# CubSat3.net
KiCad netlist of a schematic drawn in Altium Designer
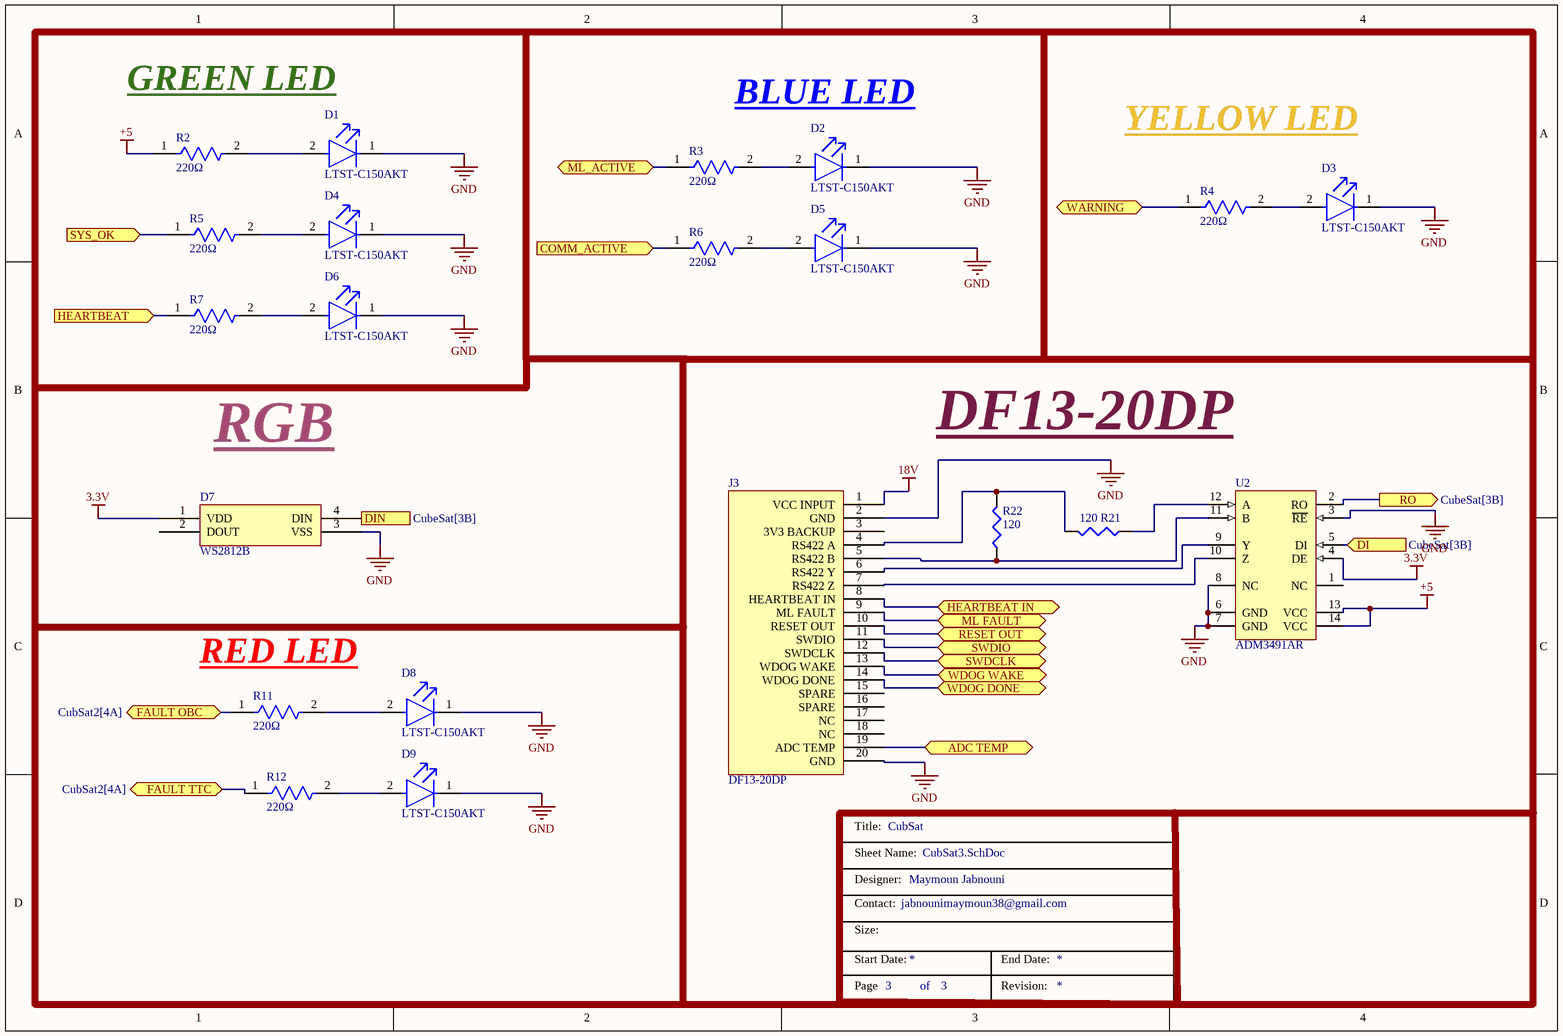
[diagram p0: CubSat3.SchDoc]

(export (version "E")
  (design (tool "Eeschema 10.0.6"))
  (components
    (comp (ref "D1")
      (value "LTST-C150AKT")
      (footprint "FP-LTST-C150AKT-MFG")
      (description "LED AMBER CLEAR SMD")
      (fields
        (field (name "MANUFACTURER") "Lite-On")
        (field (name "OCTOPART") "https://octopart.com/ltst-c150akt-lite-on-549804")
      )
      (libsource (lib "Altium Content Vault") (part "8706943c75ba83719d021d2fdc84c58"))
    )
    (comp (ref "D2")
      (value "LTST-C150AKT")
      (footprint "FP-LTST-C150AKT-MFG")
      (description "LED AMBER CLEAR SMD")
      (fields
        (field (name "MANUFACTURER") "Lite-On")
        (field (name "OCTOPART") "https://octopart.com/ltst-c150akt-lite-on-549804")
      )
      (libsource (lib "Altium Content Vault") (part "8706943c75ba83719d021d2fdc84c58"))
    )
    (comp (ref "D3")
      (value "LTST-C150AKT")
      (footprint "FP-LTST-C150AKT-MFG")
      (description "LED AMBER CLEAR SMD")
      (fields
        (field (name "MANUFACTURER") "Lite-On")
        (field (name "OCTOPART") "https://octopart.com/ltst-c150akt-lite-on-549804")
      )
      (libsource (lib "Altium Content Vault") (part "8706943c75ba83719d021d2fdc84c58"))
    )
    (comp (ref "D4")
      (value "LTST-C150AKT")
      (footprint "FP-LTST-C150AKT-MFG")
      (description "LED AMBER CLEAR SMD")
      (fields
        (field (name "MANUFACTURER") "Lite-On")
        (field (name "OCTOPART") "https://octopart.com/ltst-c150akt-lite-on-549804")
      )
      (libsource (lib "Altium Content Vault") (part "8706943c75ba83719d021d2fdc84c58"))
    )
    (comp (ref "D5")
      (value "LTST-C150AKT")
      (footprint "FP-LTST-C150AKT-MFG")
      (description "LED AMBER CLEAR SMD")
      (fields
        (field (name "MANUFACTURER") "Lite-On")
        (field (name "OCTOPART") "https://octopart.com/ltst-c150akt-lite-on-549804")
      )
      (libsource (lib "Altium Content Vault") (part "8706943c75ba83719d021d2fdc84c58"))
    )
    (comp (ref "D6")
      (value "LTST-C150AKT")
      (footprint "FP-LTST-C150AKT-MFG")
      (description "LED AMBER CLEAR SMD")
      (fields
        (field (name "MANUFACTURER") "Lite-On")
        (field (name "OCTOPART") "https://octopart.com/ltst-c150akt-lite-on-549804")
      )
      (libsource (lib "Altium Content Vault") (part "8706943c75ba83719d021d2fdc84c58"))
    )
    (comp (ref "D7") (value "WS2812B") (footprint "WS2812B") (libsource (lib "CubSat") (part "RGB_LED")))
    (comp (ref "D8")
      (value "LTST-C150AKT")
      (footprint "FP-LTST-C150AKT-MFG")
      (description "LED AMBER CLEAR SMD")
      (fields
        (field (name "MANUFACTURER") "Lite-On")
        (field (name "OCTOPART") "https://octopart.com/ltst-c150akt-lite-on-549804")
      )
      (libsource (lib "Altium Content Vault") (part "8706943c75ba83719d021d2fdc84c58"))
    )
    (comp (ref "D9")
      (value "LTST-C150AKT")
      (footprint "FP-LTST-C150AKT-MFG")
      (description "LED AMBER CLEAR SMD")
      (fields
        (field (name "MANUFACTURER") "Lite-On")
        (field (name "OCTOPART") "https://octopart.com/ltst-c150akt-lite-on-549804")
      )
      (libsource (lib "Altium Content Vault") (part "8706943c75ba83719d021d2fdc84c58"))
    )
    (comp (ref "J3")
      (value "DF13-20DP")
      (footprint "DF13-20DP")
      (libsource (lib "CubSat") (part "DF13-20DP"))
    )
    (comp (ref "R2")
      (value "220Ω")
      (footprint "FP-RMCF0603-MFG")
      (description "220Ω ±5% 0.1W 0603 Thick Film Chip Resistor AEC-Q200 compliant")
      (fields (field (name "TOLERANCE") "5%"))
      (libsource (lib "Altium Content Vault") (part "1029c3af85768c4190bb7ad29bc67b5"))
    )
    (comp (ref "R3")
      (value "220Ω")
      (footprint "FP-RMCF0603-MFG")
      (description "220Ω ±5% 0.1W 0603 Thick Film Chip Resistor AEC-Q200 compliant")
      (fields (field (name "TOLERANCE") "5%"))
      (libsource (lib "Altium Content Vault") (part "1029c3af85768c4190bb7ad29bc67b5"))
    )
    (comp (ref "R4")
      (value "220Ω")
      (footprint "FP-RMCF0603-MFG")
      (description "220Ω ±5% 0.1W 0603 Thick Film Chip Resistor AEC-Q200 compliant")
      (fields (field (name "TOLERANCE") "5%"))
      (libsource (lib "Altium Content Vault") (part "1029c3af85768c4190bb7ad29bc67b5"))
    )
    (comp (ref "R5")
      (value "220Ω")
      (footprint "FP-RMCF0603-MFG")
      (description "220Ω ±5% 0.1W 0603 Thick Film Chip Resistor AEC-Q200 compliant")
      (fields (field (name "TOLERANCE") "5%"))
      (libsource (lib "Altium Content Vault") (part "1029c3af85768c4190bb7ad29bc67b5"))
    )
    (comp (ref "R6")
      (value "220Ω")
      (footprint "FP-RMCF0603-MFG")
      (description "220Ω ±5% 0.1W 0603 Thick Film Chip Resistor AEC-Q200 compliant")
      (fields (field (name "TOLERANCE") "5%"))
      (libsource (lib "Altium Content Vault") (part "1029c3af85768c4190bb7ad29bc67b5"))
    )
    (comp (ref "R7")
      (value "220Ω")
      (footprint "FP-RMCF0603-MFG")
      (description "220Ω ±5% 0.1W 0603 Thick Film Chip Resistor AEC-Q200 compliant")
      (fields (field (name "TOLERANCE") "5%"))
      (libsource (lib "Altium Content Vault") (part "1029c3af85768c4190bb7ad29bc67b5"))
    )
    (comp (ref "R11")
      (value "220Ω")
      (footprint "FP-RMCF0603-MFG")
      (description "220Ω ±5% 0.1W 0603 Thick Film Chip Resistor AEC-Q200 compliant")
      (fields (field (name "TOLERANCE") "5%"))
      (libsource (lib "Altium Content Vault") (part "1029c3af85768c4190bb7ad29bc67b5"))
    )
    (comp (ref "R12")
      (value "220Ω")
      (footprint "FP-RMCF0603-MFG")
      (description "220Ω ±5% 0.1W 0603 Thick Film Chip Resistor AEC-Q200 compliant")
      (fields (field (name "TOLERANCE") "5%"))
      (libsource (lib "Altium Content Vault") (part "1029c3af85768c4190bb7ad29bc67b5"))
    )
    (comp (ref "R21")
      (value "120")
      (footprint "J1-0603")
      (description "Resistor")
      (fields (field (name "Comment") "Res3") (field (name "PUBLISHER") "Altium Limited"))
      (libsource (lib "Miscellaneous Devices") (part "Res3"))
    )
    (comp (ref "R22")
      (value "120")
      (footprint "J1-0603")
      (description "Resistor")
      (fields (field (name "Comment") "Res3") (field (name "PUBLISHER") "Altium Limited"))
      (libsource (lib "Miscellaneous Devices") (part "Res3"))
    )
    (comp (ref "U2")
      (value "ADM3491AR")
      (footprint "ADI-R-14_N")
      (fields (field (name "MANUFACTURER") "Analog Devices"))
      (libsource (lib "Altium Content Vault") (part "ADI-ADM3491-R-14"))
    )
  )
  (nets
    (net (code "1") (name "+5") (class "Default")
      (node (ref "R2") (pin "1") (pinfunction "1_1") (pintype "passive"))
      (node (ref "U2") (pin "13") (pinfunction "VCC_13") (pintype "power_in"))
      (node (ref "U2") (pin "14") (pinfunction "VCC_14") (pintype "power_in"))
    )
    (net (code "2") (name "/ADC TEMP") (class "Default")
      (node (ref "J3") (pin "19") (pinfunction "ADC_TEMP_19") (pintype "passive"))
    )
    (net (code "3") (name "/COMM_ACTIVE") (class "Default")
      (node (ref "R6") (pin "1") (pinfunction "1_1") (pintype "passive"))
    )
    (net (code "4") (name "/DI") (class "Default")
      (node (ref "U2") (pin "5") (pinfunction "DI_5") (pintype "input"))
    )
    (net (code "5") (name "/DIN") (class "Default")
      (node (ref "D7") (pin "4") (pinfunction "DIN_4") (pintype "passive"))
    )
    (net (code "6") (name "/FAULT OBC") (class "Default")
      (node (ref "R11") (pin "1") (pinfunction "1_1") (pintype "passive"))
    )
    (net (code "7") (name "/FAULT TTC") (class "Default")
      (node (ref "R12") (pin "1") (pinfunction "1_1") (pintype "passive"))
    )
    (net (code "8") (name "/HEARTBEAT") (class "Default")
      (node (ref "R7") (pin "1") (pinfunction "1_1") (pintype "passive"))
    )
    (net (code "9") (name "/HEARTBEAT IN") (class "Default")
      (node (ref "J3") (pin "8") (pinfunction "HEARTBEAT_IN_8") (pintype "passive"))
    )
    (net (code "10") (name "/ML FAULT") (class "Default")
      (node (ref "J3") (pin "9") (pinfunction "ML_FAULT_9") (pintype "passive"))
    )
    (net (code "11") (name "/ML_ACTIVE") (class "Default")
      (node (ref "R3") (pin "1") (pinfunction "1_1") (pintype "passive"))
    )
    (net (code "12") (name "/RESET OUT") (class "Default")
      (node (ref "J3") (pin "10") (pinfunction "RESET_OUT_10") (pintype "passive"))
    )
    (net (code "13") (name "/RO") (class "Default")
      (node (ref "U2") (pin "2") (pinfunction "RO_2") (pintype "tri_state"))
    )
    (net (code "14") (name "/SWDCLK") (class "Default")
      (node (ref "J3") (pin "12") (pinfunction "SWDCLK_12") (pintype "passive"))
    )
    (net (code "15") (name "/SWDIO") (class "Default")
      (node (ref "J3") (pin "11") (pinfunction "SWDIO_11") (pintype "passive"))
    )
    (net (code "16") (name "/SYS_OK") (class "Default")
      (node (ref "R5") (pin "1") (pinfunction "1_1") (pintype "passive"))
    )
    (net (code "17") (name "/WARNING") (class "Default")
      (node (ref "R4") (pin "1") (pinfunction "1_1") (pintype "passive"))
    )
    (net (code "18") (name "/WDOG DONE") (class "Default")
      (node (ref "J3") (pin "14") (pinfunction "WDOG_DONE_14") (pintype "passive"))
    )
    (net (code "19") (name "/WDOG WAKE") (class "Default")
      (node (ref "J3") (pin "13") (pinfunction "WDOG_WAKE_13") (pintype "passive"))
    )
    (net (code "20") (name "3.3V") (class "Default")
      (node (ref "D7") (pin "1") (pinfunction "VDD_1") (pintype "passive"))
      (node (ref "U2") (pin "4") (pinfunction "DE_4") (pintype "input"))
    )
    (net (code "21") (name "18V") (class "Default")
      (node (ref "J3") (pin "1") (pinfunction "VCC_INPUT_1") (pintype "passive"))
    )
    (net (code "22") (name "GND") (class "Default")
      (node (ref "D1") (pin "1") (pinfunction "C_1") (pintype "passive"))
      (node (ref "D2") (pin "1") (pinfunction "C_1") (pintype "passive"))
      (node (ref "D3") (pin "1") (pinfunction "C_1") (pintype "passive"))
      (node (ref "D4") (pin "1") (pinfunction "C_1") (pintype "passive"))
      (node (ref "D5") (pin "1") (pinfunction "C_1") (pintype "passive"))
      (node (ref "D6") (pin "1") (pinfunction "C_1") (pintype "passive"))
      (node (ref "D7") (pin "3") (pinfunction "VSS_3") (pintype "passive"))
      (node (ref "D8") (pin "1") (pinfunction "C_1") (pintype "passive"))
      (node (ref "D9") (pin "1") (pinfunction "C_1") (pintype "passive"))
      (node (ref "J3") (pin "2") (pinfunction "GND_2") (pintype "passive"))
      (node (ref "J3") (pin "20") (pinfunction "GND_20") (pintype "passive"))
      (node (ref "U2") (pin "3") (pinfunction "~{RE}_3") (pintype "input"))
      (node (ref "U2") (pin "6") (pinfunction "GND_6") (pintype "power_in"))
      (node (ref "U2") (pin "7") (pinfunction "GND_7") (pintype "power_in"))
      (node (ref "U2") (pin "8") (pinfunction "NC_8") (pintype "passive"))
    )
    (net (code "23") (name "Net-(D1-A)") (class "Default")
      (node (ref "D1") (pin "2") (pinfunction "A_2") (pintype "passive"))
      (node (ref "R2") (pin "2") (pinfunction "2_2") (pintype "passive"))
    )
    (net (code "24") (name "Net-(D2-A)") (class "Default")
      (node (ref "D2") (pin "2") (pinfunction "A_2") (pintype "passive"))
      (node (ref "R3") (pin "2") (pinfunction "2_2") (pintype "passive"))
    )
    (net (code "25") (name "Net-(D3-A)") (class "Default")
      (node (ref "D3") (pin "2") (pinfunction "A_2") (pintype "passive"))
      (node (ref "R4") (pin "2") (pinfunction "2_2") (pintype "passive"))
    )
    (net (code "26") (name "Net-(D4-A)") (class "Default")
      (node (ref "D4") (pin "2") (pinfunction "A_2") (pintype "passive"))
      (node (ref "R5") (pin "2") (pinfunction "2_2") (pintype "passive"))
    )
    (net (code "27") (name "Net-(D5-A)") (class "Default")
      (node (ref "D5") (pin "2") (pinfunction "A_2") (pintype "passive"))
      (node (ref "R6") (pin "2") (pinfunction "2_2") (pintype "passive"))
    )
    (net (code "28") (name "Net-(D6-A)") (class "Default")
      (node (ref "D6") (pin "2") (pinfunction "A_2") (pintype "passive"))
      (node (ref "R7") (pin "2") (pinfunction "2_2") (pintype "passive"))
    )
    (net (code "29") (name "Net-(D8-A)") (class "Default")
      (node (ref "D8") (pin "2") (pinfunction "A_2") (pintype "passive"))
      (node (ref "R11") (pin "2") (pinfunction "2_2") (pintype "passive"))
    )
    (net (code "30") (name "Net-(D9-A)") (class "Default")
      (node (ref "D9") (pin "2") (pinfunction "A_2") (pintype "passive"))
      (node (ref "R12") (pin "2") (pinfunction "2_2") (pintype "passive"))
    )
    (net (code "31") (name "Net-(J3-RS422_A)") (class "Default")
      (node (ref "J3") (pin "4") (pinfunction "RS422_A_4") (pintype "passive"))
      (node (ref "R21") (pin "2") (pinfunction "2_2") (pintype "passive"))
      (node (ref "R22") (pin "2") (pinfunction "2_2") (pintype "passive"))
    )
    (net (code "32") (name "Net-(J3-RS422_B)") (class "Default")
      (node (ref "J3") (pin "5") (pinfunction "RS422_B_5") (pintype "passive"))
      (node (ref "R22") (pin "1") (pinfunction "1_1") (pintype "passive"))
      (node (ref "U2") (pin "11") (pinfunction "B_11") (pintype "input"))
    )
    (net (code "33") (name "Net-(J3-RS422_Y)") (class "Default")
      (node (ref "J3") (pin "6") (pinfunction "RS422_Y_6") (pintype "passive"))
      (node (ref "U2") (pin "9") (pinfunction "Y_9") (pintype "tri_state"))
    )
    (net (code "34") (name "Net-(J3-RS422_Z)") (class "Default")
      (node (ref "J3") (pin "7") (pinfunction "RS422_Z_7") (pintype "passive"))
      (node (ref "U2") (pin "10") (pinfunction "Z_10") (pintype "tri_state"))
    )
    (net (code "35") (name "Net-(U2-A)") (class "Default")
      (node (ref "R21") (pin "1") (pinfunction "1_1") (pintype "passive"))
      (node (ref "U2") (pin "12") (pinfunction "A_12") (pintype "input"))
    )
    (net (code "36") (name "unconnected-(D7-DOUT-Pad2)") (class "Default")
      (node (ref "D7") (pin "2") (pinfunction "DOUT_2") (pintype "passive"))
    )
    (net (code "37") (name "unconnected-(J3-3V3_BACKUP-Pad3)") (class "Default")
      (node (ref "J3") (pin "3") (pinfunction "3V3_BACKUP_3") (pintype "passive"))
    )
    (net (code "38") (name "unconnected-(J3-NC-Pad17)") (class "Default")
      (node (ref "J3") (pin "17") (pinfunction "NC_17") (pintype "passive"))
    )
    (net (code "39") (name "unconnected-(J3-NC-Pad18)") (class "Default")
      (node (ref "J3") (pin "18") (pinfunction "NC_18") (pintype "passive"))
    )
    (net (code "40") (name "unconnected-(J3-SPARE-Pad15)") (class "Default")
      (node (ref "J3") (pin "15") (pinfunction "SPARE_15") (pintype "passive"))
    )
    (net (code "41") (name "unconnected-(J3-SPARE-Pad16)") (class "Default")
      (node (ref "J3") (pin "16") (pinfunction "SPARE_16") (pintype "passive"))
    )
    (net (code "42") (name "unconnected-(U2-NC-Pad1)") (class "Default")
      (node (ref "U2") (pin "1") (pinfunction "NC_1") (pintype "passive"))
    )
  )
)
